# power-berry_analog.net
KiCad netlist of a schematic drawn in Altium Designer
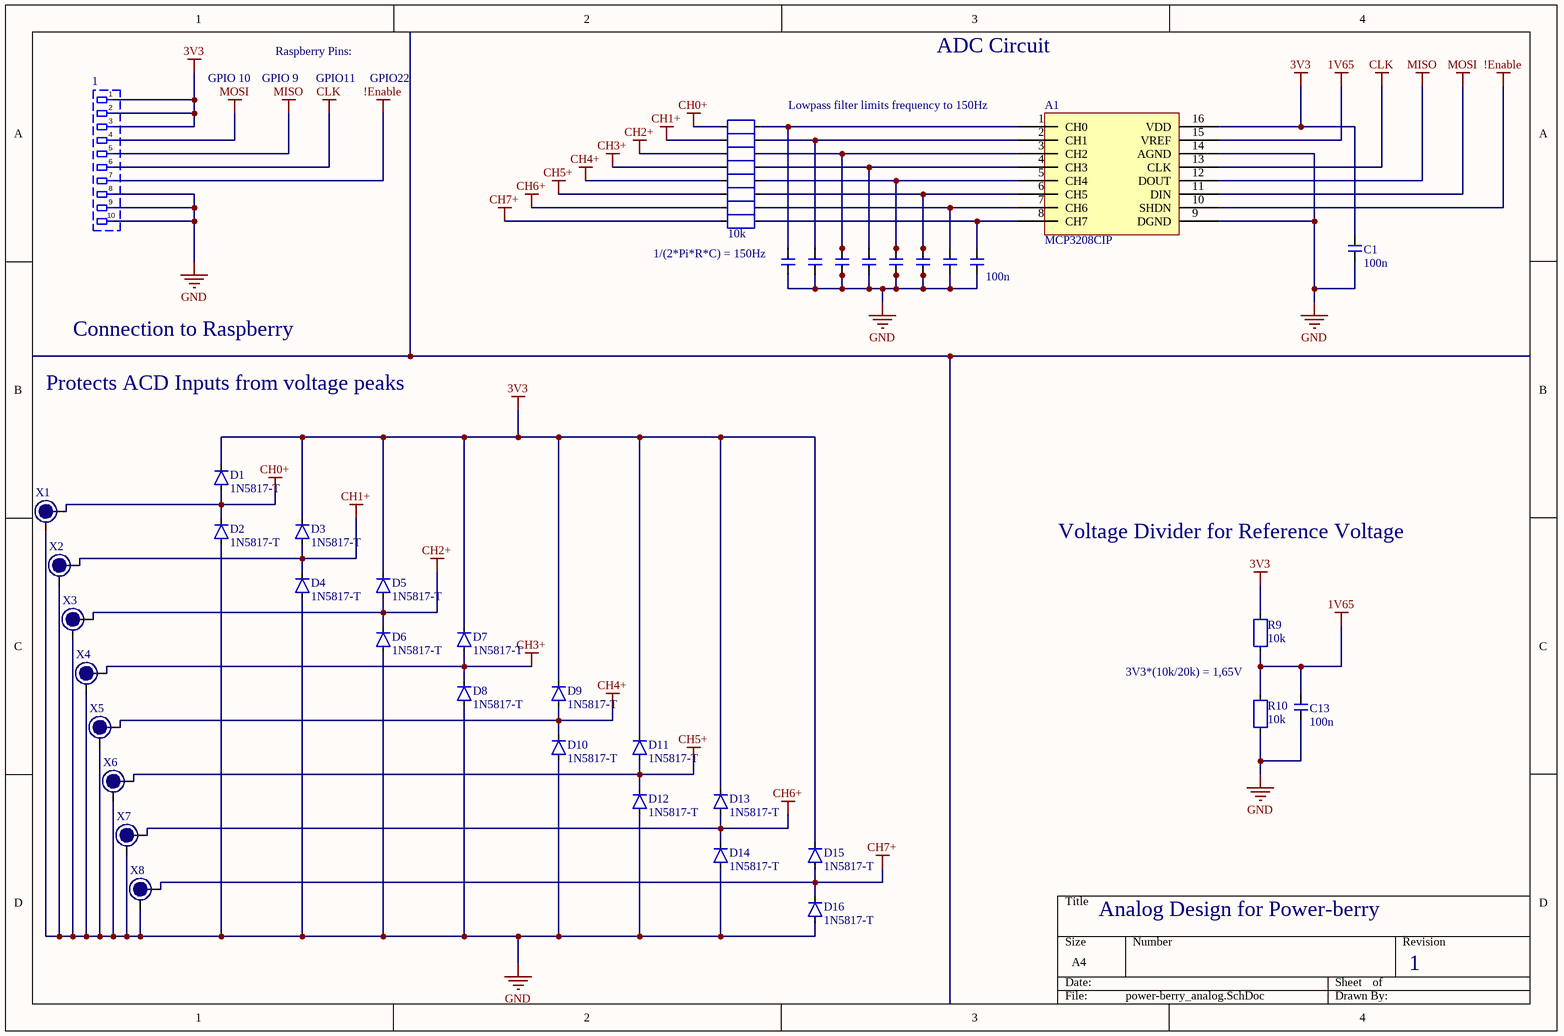
[diagram p0: power-berry_analog.SchDoc]

(export (version "E")
  (design (tool "Eeschema 10.0.6"))
  (components
    (comp (ref "1") (value "Connection to Raspberry") (libsource (lib "KONTAKT") (part "STIFTLEISTE_10")))
    (comp (ref "A1") (value "MCP3208CIP") (libsource (lib "Schlib1") (part "MCP3208CIP")))
    (comp (ref "C1") (value "100n") (footprint "SMD 1206") (libsource (lib "Passiv") (part "KOND")))
    (comp (ref "C2") (value "100n") (footprint "SMD 1206") (libsource (lib "Passiv") (part "KOND")))
    (comp (ref "C3") (value "100n") (footprint "SMD 1206") (libsource (lib "Passiv") (part "KOND")))
    (comp (ref "C4") (value "100n") (footprint "SMD 1206") (libsource (lib "Passiv") (part "KOND")))
    (comp (ref "C5") (value "100n") (footprint "SMD 1206") (libsource (lib "Passiv") (part "KOND")))
    (comp (ref "C6") (value "100n") (footprint "SMD 1206") (libsource (lib "Passiv") (part "KOND")))
    (comp (ref "C7") (value "100n") (footprint "SMD 1206") (libsource (lib "Passiv") (part "KOND")))
    (comp (ref "C8") (value "100n") (footprint "SMD 1206") (libsource (lib "Passiv") (part "KOND")))
    (comp (ref "C9") (value "100n") (footprint "SMD 1206") (libsource (lib "Passiv") (part "KOND")))
    (comp (ref "C10") (value "100n") (footprint "SMD 1206") (libsource (lib "Passiv") (part "KOND")))
    (comp (ref "C11") (value "100n") (footprint "SMD 1206") (libsource (lib "Passiv") (part "KOND")))
    (comp (ref "C12") (value "100n") (footprint "SMD 1206") (libsource (lib "Passiv") (part "KOND")))
    (comp (ref "C13") (value "100n") (footprint "SMD 1206") (libsource (lib "Passiv") (part "KOND")))
    (comp (ref "D1")
      (value "1N5817-T")
      (footprint "SMD 0204 MELF D")
      (libsource (lib "Passiv") (part "DIODE"))
    )
    (comp (ref "D2")
      (value "1N5817-T")
      (footprint "SMD 0204 MELF D")
      (libsource (lib "Passiv") (part "DIODE"))
    )
    (comp (ref "D3")
      (value "1N5817-T")
      (footprint "SMD 0204 MELF D")
      (libsource (lib "Passiv") (part "DIODE"))
    )
    (comp (ref "D4")
      (value "1N5817-T")
      (footprint "SMD 0204 MELF D")
      (libsource (lib "Passiv") (part "DIODE"))
    )
    (comp (ref "D5")
      (value "1N5817-T")
      (footprint "SMD 0204 MELF D")
      (libsource (lib "Passiv") (part "DIODE"))
    )
    (comp (ref "D6")
      (value "1N5817-T")
      (footprint "SMD 0204 MELF D")
      (libsource (lib "Passiv") (part "DIODE"))
    )
    (comp (ref "D7")
      (value "1N5817-T")
      (footprint "SMD 0204 MELF D")
      (libsource (lib "Passiv") (part "DIODE"))
    )
    (comp (ref "D8")
      (value "1N5817-T")
      (footprint "SMD 0204 MELF D")
      (libsource (lib "Passiv") (part "DIODE"))
    )
    (comp (ref "D9")
      (value "1N5817-T")
      (footprint "SMD 0204 MELF D")
      (libsource (lib "Passiv") (part "DIODE"))
    )
    (comp (ref "D10")
      (value "1N5817-T")
      (footprint "SMD 0204 MELF D")
      (libsource (lib "Passiv") (part "DIODE"))
    )
    (comp (ref "D11")
      (value "1N5817-T")
      (footprint "SMD 0204 MELF D")
      (libsource (lib "Passiv") (part "DIODE"))
    )
    (comp (ref "D12")
      (value "1N5817-T")
      (footprint "SMD 0204 MELF D")
      (libsource (lib "Passiv") (part "DIODE"))
    )
    (comp (ref "D13")
      (value "1N5817-T")
      (footprint "SMD 0204 MELF D")
      (libsource (lib "Passiv") (part "DIODE"))
    )
    (comp (ref "D14")
      (value "1N5817-T")
      (footprint "SMD 0204 MELF D")
      (libsource (lib "Passiv") (part "DIODE"))
    )
    (comp (ref "D15")
      (value "1N5817-T")
      (footprint "SMD 0204 MELF D")
      (libsource (lib "Passiv") (part "DIODE"))
    )
    (comp (ref "D16")
      (value "1N5817-T")
      (footprint "SMD 0204 MELF D")
      (libsource (lib "Passiv") (part "DIODE"))
    )
    (comp (ref "R1") (value "WID") (footprint "SMD 1206") (libsource (lib "Passiv") (part "WID")))
    (comp (ref "R2") (value "WID") (footprint "SMD 1206") (libsource (lib "Passiv") (part "WID")))
    (comp (ref "R3") (value "WID") (footprint "SMD 1206") (libsource (lib "Passiv") (part "WID")))
    (comp (ref "R4") (value "WID") (footprint "SMD 1206") (libsource (lib "Passiv") (part "WID")))
    (comp (ref "R5") (value "WID") (footprint "SMD 1206") (libsource (lib "Passiv") (part "WID")))
    (comp (ref "R6") (value "WID") (footprint "SMD 1206") (libsource (lib "Passiv") (part "WID")))
    (comp (ref "R7") (value "WID") (footprint "SMD 1206") (libsource (lib "Passiv") (part "WID")))
    (comp (ref "R8") (value "10k") (footprint "SMD 1206") (libsource (lib "Passiv") (part "WID")))
    (comp (ref "R9") (value "10k") (footprint "SMD 1206") (libsource (lib "") (part "WID_1")))
    (comp (ref "R10") (value "10k") (footprint "SMD 1206") (libsource (lib "") (part "WID_1")))
    (comp (ref "X1")
      (value "Hohlbuchse1")
      (footprint "BU HOL 1")
      (libsource (lib "KONTAKT") (part "Hohlbuchse1"))
    )
    (comp (ref "X2")
      (value "Hohlbuchse1")
      (footprint "BU HOL 1")
      (libsource (lib "KONTAKT") (part "Hohlbuchse1"))
    )
    (comp (ref "X3")
      (value "Hohlbuchse1")
      (footprint "BU HOL 1")
      (libsource (lib "KONTAKT") (part "Hohlbuchse1"))
    )
    (comp (ref "X4")
      (value "Hohlbuchse1")
      (footprint "BU HOL 1")
      (libsource (lib "KONTAKT") (part "Hohlbuchse1"))
    )
    (comp (ref "X5")
      (value "Hohlbuchse1")
      (footprint "BU HOL 1")
      (libsource (lib "KONTAKT") (part "Hohlbuchse1"))
    )
    (comp (ref "X6")
      (value "Hohlbuchse1")
      (footprint "BU HOL 1")
      (libsource (lib "KONTAKT") (part "Hohlbuchse1"))
    )
    (comp (ref "X7")
      (value "Hohlbuchse1")
      (footprint "BU HOL 1")
      (libsource (lib "KONTAKT") (part "Hohlbuchse1"))
    )
    (comp (ref "X8")
      (value "Hohlbuchse1")
      (footprint "BU HOL 1")
      (libsource (lib "KONTAKT") (part "Hohlbuchse1"))
    )
  )
  (nets
    (net (code "1") (name "!Enable") (class "Default")
      (node (ref "1") (pin "7") (pinfunction "1_7") (pintype "passive"))
      (node (ref "A1") (pin "10") (pinfunction "SHDN_10") (pintype "passive"))
    )
    (net (code "2") (name "1V65") (class "Default")
      (node (ref "A1") (pin "15") (pinfunction "VREF_15") (pintype "passive"))
      (node (ref "C13") (pin "2") (pintype "passive"))
      (node (ref "R10") (pin "2") (pintype "passive"))
      (node (ref "R9") (pin "1") (pintype "passive"))
    )
    (net (code "3") (name "3V3") (class "Default")
      (node (ref "1") (pin "1") (pinfunction "1_1") (pintype "passive"))
      (node (ref "1") (pin "2") (pinfunction "1_2") (pintype "passive"))
      (node (ref "1") (pin "3") (pinfunction "1_3") (pintype "passive"))
      (node (ref "A1") (pin "16") (pinfunction "VDD_16") (pintype "passive"))
      (node (ref "C1") (pin "2") (pintype "passive"))
      (node (ref "D1") (pin "2") (pintype "passive"))
      (node (ref "D11") (pin "2") (pintype "passive"))
      (node (ref "D13") (pin "2") (pintype "passive"))
      (node (ref "D15") (pin "2") (pintype "passive"))
      (node (ref "D3") (pin "2") (pintype "passive"))
      (node (ref "D5") (pin "2") (pintype "passive"))
      (node (ref "D7") (pin "2") (pintype "passive"))
      (node (ref "D9") (pin "2") (pintype "passive"))
      (node (ref "R9") (pin "2") (pintype "passive"))
    )
    (net (code "4") (name "CH0+") (class "Default")
      (node (ref "D1") (pin "1") (pintype "passive"))
      (node (ref "D2") (pin "2") (pintype "passive"))
      (node (ref "R1") (pin "2") (pintype "passive"))
      (node (ref "X1") (pin "1") (pinfunction "1_1") (pintype "passive"))
    )
    (net (code "5") (name "CH1+") (class "Default")
      (node (ref "D3") (pin "1") (pintype "passive"))
      (node (ref "D4") (pin "2") (pintype "passive"))
      (node (ref "R2") (pin "2") (pintype "passive"))
      (node (ref "X2") (pin "1") (pinfunction "1_1") (pintype "passive"))
    )
    (net (code "6") (name "CH2+") (class "Default")
      (node (ref "D5") (pin "1") (pintype "passive"))
      (node (ref "D6") (pin "2") (pintype "passive"))
      (node (ref "R3") (pin "2") (pintype "passive"))
      (node (ref "X3") (pin "1") (pinfunction "1_1") (pintype "passive"))
    )
    (net (code "7") (name "CH3+") (class "Default")
      (node (ref "D7") (pin "1") (pintype "passive"))
      (node (ref "D8") (pin "2") (pintype "passive"))
      (node (ref "R4") (pin "2") (pintype "passive"))
      (node (ref "X4") (pin "1") (pinfunction "1_1") (pintype "passive"))
    )
    (net (code "8") (name "CH4+") (class "Default")
      (node (ref "D10") (pin "2") (pintype "passive"))
      (node (ref "D9") (pin "1") (pintype "passive"))
      (node (ref "R5") (pin "2") (pintype "passive"))
      (node (ref "X5") (pin "1") (pinfunction "1_1") (pintype "passive"))
    )
    (net (code "9") (name "CH5+") (class "Default")
      (node (ref "D11") (pin "1") (pintype "passive"))
      (node (ref "D12") (pin "2") (pintype "passive"))
      (node (ref "R6") (pin "2") (pintype "passive"))
      (node (ref "X6") (pin "1") (pinfunction "1_1") (pintype "passive"))
    )
    (net (code "10") (name "CH6+") (class "Default")
      (node (ref "D13") (pin "1") (pintype "passive"))
      (node (ref "D14") (pin "2") (pintype "passive"))
      (node (ref "R7") (pin "2") (pintype "passive"))
      (node (ref "X7") (pin "1") (pinfunction "1_1") (pintype "passive"))
    )
    (net (code "11") (name "CH7+") (class "Default")
      (node (ref "D15") (pin "1") (pintype "passive"))
      (node (ref "D16") (pin "2") (pintype "passive"))
      (node (ref "R8") (pin "2") (pintype "passive"))
      (node (ref "X8") (pin "1") (pinfunction "1_1") (pintype "passive"))
    )
    (net (code "12") (name "CLK") (class "Default")
      (node (ref "1") (pin "6") (pinfunction "1_6") (pintype "passive"))
      (node (ref "A1") (pin "13") (pinfunction "CLK_13") (pintype "passive"))
    )
    (net (code "13") (name "GND") (class "Default")
      (node (ref "1") (pin "10") (pinfunction "1_10") (pintype "passive"))
      (node (ref "1") (pin "8") (pinfunction "1_8") (pintype "passive"))
      (node (ref "1") (pin "9") (pinfunction "1_9") (pintype "passive"))
      (node (ref "A1") (pin "14") (pinfunction "AGND_14") (pintype "passive"))
      (node (ref "A1") (pin "9") (pinfunction "DGND_9") (pintype "passive"))
      (node (ref "C1") (pin "1") (pintype "passive"))
      (node (ref "C10") (pin "1") (pintype "passive"))
      (node (ref "C11") (pin "1") (pintype "passive"))
      (node (ref "C12") (pin "1") (pintype "passive"))
      (node (ref "C13") (pin "1") (pintype "passive"))
      (node (ref "C2") (pin "1") (pintype "passive"))
      (node (ref "C3") (pin "1") (pintype "passive"))
      (node (ref "C4") (pin "1") (pintype "passive"))
      (node (ref "C5") (pin "1") (pintype "passive"))
      (node (ref "C6") (pin "1") (pintype "passive"))
      (node (ref "C7") (pin "1") (pintype "passive"))
      (node (ref "C8") (pin "1") (pintype "passive"))
      (node (ref "C9") (pin "1") (pintype "passive"))
      (node (ref "D10") (pin "1") (pintype "passive"))
      (node (ref "D12") (pin "1") (pintype "passive"))
      (node (ref "D14") (pin "1") (pintype "passive"))
      (node (ref "D16") (pin "1") (pintype "passive"))
      (node (ref "D2") (pin "1") (pintype "passive"))
      (node (ref "D4") (pin "1") (pintype "passive"))
      (node (ref "D6") (pin "1") (pintype "passive"))
      (node (ref "D8") (pin "1") (pintype "passive"))
      (node (ref "R10") (pin "1") (pintype "passive"))
      (node (ref "X1") (pin "2") (pinfunction "2_2") (pintype "passive"))
      (node (ref "X2") (pin "2") (pinfunction "2_2") (pintype "passive"))
      (node (ref "X3") (pin "2") (pinfunction "2_2") (pintype "passive"))
      (node (ref "X4") (pin "2") (pinfunction "2_2") (pintype "passive"))
      (node (ref "X5") (pin "2") (pinfunction "2_2") (pintype "passive"))
      (node (ref "X6") (pin "2") (pinfunction "2_2") (pintype "passive"))
      (node (ref "X7") (pin "2") (pinfunction "2_2") (pintype "passive"))
      (node (ref "X8") (pin "2") (pinfunction "2_2") (pintype "passive"))
    )
    (net (code "14") (name "MISO") (class "Default")
      (node (ref "1") (pin "5") (pinfunction "1_5") (pintype "passive"))
      (node (ref "A1") (pin "12") (pinfunction "DOUT_12") (pintype "passive"))
    )
    (net (code "15") (name "MOSI") (class "Default")
      (node (ref "1") (pin "4") (pinfunction "1_4") (pintype "passive"))
      (node (ref "A1") (pin "11") (pinfunction "DIN_11") (pintype "passive"))
    )
    (net (code "16") (name "Net-(A1-CH0)") (class "Default")
      (node (ref "A1") (pin "1") (pinfunction "CH0_1") (pintype "passive"))
      (node (ref "C2") (pin "2") (pintype "passive"))
      (node (ref "R1") (pin "1") (pintype "passive"))
    )
    (net (code "17") (name "Net-(A1-CH1)") (class "Default")
      (node (ref "A1") (pin "2") (pinfunction "CH1_2") (pintype "passive"))
      (node (ref "C3") (pin "2") (pintype "passive"))
      (node (ref "R2") (pin "1") (pintype "passive"))
    )
    (net (code "18") (name "Net-(A1-CH2)") (class "Default")
      (node (ref "A1") (pin "3") (pinfunction "CH2_3") (pintype "passive"))
      (node (ref "C4") (pin "2") (pintype "passive"))
      (node (ref "C5") (pin "2") (pintype "passive"))
      (node (ref "R3") (pin "1") (pintype "passive"))
    )
    (net (code "19") (name "Net-(A1-CH3)") (class "Default")
      (node (ref "A1") (pin "4") (pinfunction "CH3_4") (pintype "passive"))
      (node (ref "C6") (pin "2") (pintype "passive"))
      (node (ref "R4") (pin "1") (pintype "passive"))
    )
    (net (code "20") (name "Net-(A1-CH4)") (class "Default")
      (node (ref "A1") (pin "5") (pinfunction "CH4_5") (pintype "passive"))
      (node (ref "C7") (pin "2") (pintype "passive"))
      (node (ref "C8") (pin "2") (pintype "passive"))
      (node (ref "R5") (pin "1") (pintype "passive"))
    )
    (net (code "21") (name "Net-(A1-CH5)") (class "Default")
      (node (ref "A1") (pin "6") (pinfunction "CH5_6") (pintype "passive"))
      (node (ref "C10") (pin "2") (pintype "passive"))
      (node (ref "C9") (pin "2") (pintype "passive"))
      (node (ref "R6") (pin "1") (pintype "passive"))
    )
    (net (code "22") (name "Net-(A1-CH6)") (class "Default")
      (node (ref "A1") (pin "7") (pinfunction "CH6_7") (pintype "passive"))
      (node (ref "C11") (pin "2") (pintype "passive"))
      (node (ref "R7") (pin "1") (pintype "passive"))
    )
    (net (code "23") (name "Net-(A1-CH7)") (class "Default")
      (node (ref "A1") (pin "8") (pinfunction "CH7_8") (pintype "passive"))
      (node (ref "C12") (pin "2") (pintype "passive"))
      (node (ref "R8") (pin "1") (pintype "passive"))
    )
  )
)
